# mA.net
KiCad netlist of a schematic drawn in Altium Designer
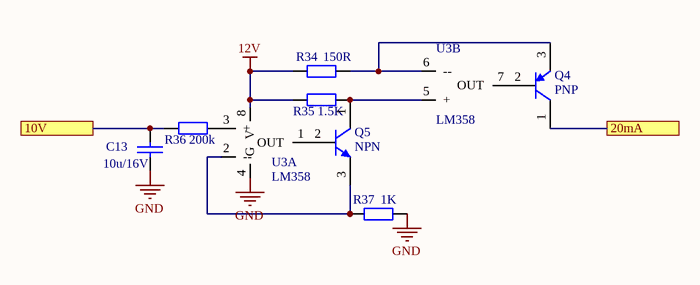
[diagram p0: mA.SchDoc]

(export (version "E")
  (design (tool "Eeschema 10.0.6"))
  (components
    (comp (ref "C13")
      (value "10u/16V")
      (footprint "1206")
      (description "Capacitor")
      (libsource (lib "*") (part "CAP"))
    )
    (comp (ref "Q4")
      (value "PNP")
      (footprint "SOT23")
      (description "PNP Bipolar Transistor")
      (fields (field (name "PUBLISHER") "Altium Limited"))
      (libsource (lib "Miscellaneous Devices") (part "PNP"))
    )
    (comp (ref "Q5")
      (value "NPN")
      (footprint "SOT23")
      (description "NPN Bipolar Transistor")
      (fields (field (name "PUBLISHER") "Altium Limited"))
      (libsource (lib "Miscellaneous Devices") (part "NPN"))
    )
    (comp (ref "R34")
      (value "150R")
      (footprint "0805R")
      (description "Resistor")
      (fields (field (name "PUBLISHER") "Altium Limited"))
      (libsource (lib "Miscellaneous Devices") (part "res"))
    )
    (comp (ref "R35")
      (value "1.5K")
      (footprint "0805R")
      (description "Resistor")
      (fields (field (name "PUBLISHER") "Altium Limited"))
      (libsource (lib "Miscellaneous Devices") (part "res"))
    )
    (comp (ref "R36")
      (value "200k")
      (footprint "0805R")
      (description "Resistor")
      (fields (field (name "PUBLISHER") "Altium Limited"))
      (libsource (lib "Miscellaneous Devices") (part "res"))
    )
    (comp (ref "R37")
      (value "1K")
      (footprint "0805R")
      (description "Resistor")
      (fields (field (name "PUBLISHER") "Altium Limited"))
      (libsource (lib "Miscellaneous Devices") (part "res"))
    )
    (comp (ref "U3") (value "LM358") (footprint "SOP-08") (libsource (lib "*") (part "LM358")))
  )
  (nets
    (net (code "1") (name "/10V") (class "Default")
      (node (ref "C13") (pin "1") (pinfunction "1_1") (pintype "passive"))
      (node (ref "R36") (pin "2") (pinfunction "2_2") (pintype "passive"))
    )
    (net (code "2") (name "/20mA") (class "Default")
      (node (ref "Q4") (pin "1") (pinfunction "C_1") (pintype "passive"))
    )
    (net (code "3") (name "12V") (class "Default")
      (node (ref "R34") (pin "2") (pinfunction "2_2") (pintype "passive"))
      (node (ref "R35") (pin "2") (pinfunction "2_2") (pintype "passive"))
      (node (ref "U3") (pin "8") (pinfunction "V_8") (pintype "passive"))
    )
    (net (code "4") (name "GND") (class "Default")
      (node (ref "C13") (pin "2") (pinfunction "2_2") (pintype "passive"))
      (node (ref "R37") (pin "1") (pinfunction "1_1") (pintype "passive"))
      (node (ref "U3") (pin "4") (pinfunction "G_4") (pintype "passive"))
    )
    (net (code "5") (name "Net-(Q4-B)") (class "Default")
      (node (ref "Q4") (pin "2") (pinfunction "B_2") (pintype "passive"))
      (node (ref "U3") (pin "7") (pinfunction "OUT_7") (pintype "passive"))
    )
    (net (code "6") (name "Net-(Q4-E)") (class "Default")
      (node (ref "Q4") (pin "3") (pinfunction "E_3") (pintype "passive"))
      (node (ref "R34") (pin "1") (pinfunction "1_1") (pintype "passive"))
      (node (ref "U3") (pin "6") (pinfunction "--_6") (pintype "passive"))
    )
    (net (code "7") (name "Net-(Q5-B)") (class "Default")
      (node (ref "Q5") (pin "2") (pinfunction "B_2") (pintype "passive"))
      (node (ref "U3") (pin "1") (pinfunction "OUT_1") (pintype "passive"))
    )
    (net (code "8") (name "Net-(Q5-C)") (class "Default")
      (node (ref "Q5") (pin "1") (pinfunction "C_1") (pintype "passive"))
      (node (ref "R35") (pin "1") (pinfunction "1_1") (pintype "passive"))
      (node (ref "U3") (pin "5") (pinfunction "+_5") (pintype "passive"))
    )
    (net (code "9") (name "Net-(Q5-E)") (class "Default")
      (node (ref "Q5") (pin "3") (pinfunction "E_3") (pintype "passive"))
      (node (ref "R37") (pin "2") (pinfunction "2_2") (pintype "passive"))
      (node (ref "U3") (pin "2") (pinfunction "--_2") (pintype "passive"))
    )
    (net (code "10") (name "Net-(U3A-+)") (class "Default")
      (node (ref "R36") (pin "1") (pinfunction "1_1") (pintype "passive"))
      (node (ref "U3") (pin "3") (pinfunction "+_3") (pintype "passive"))
    )
  )
)
